# Underglow.net
KiCad netlist of a schematic drawn in Altium Designer
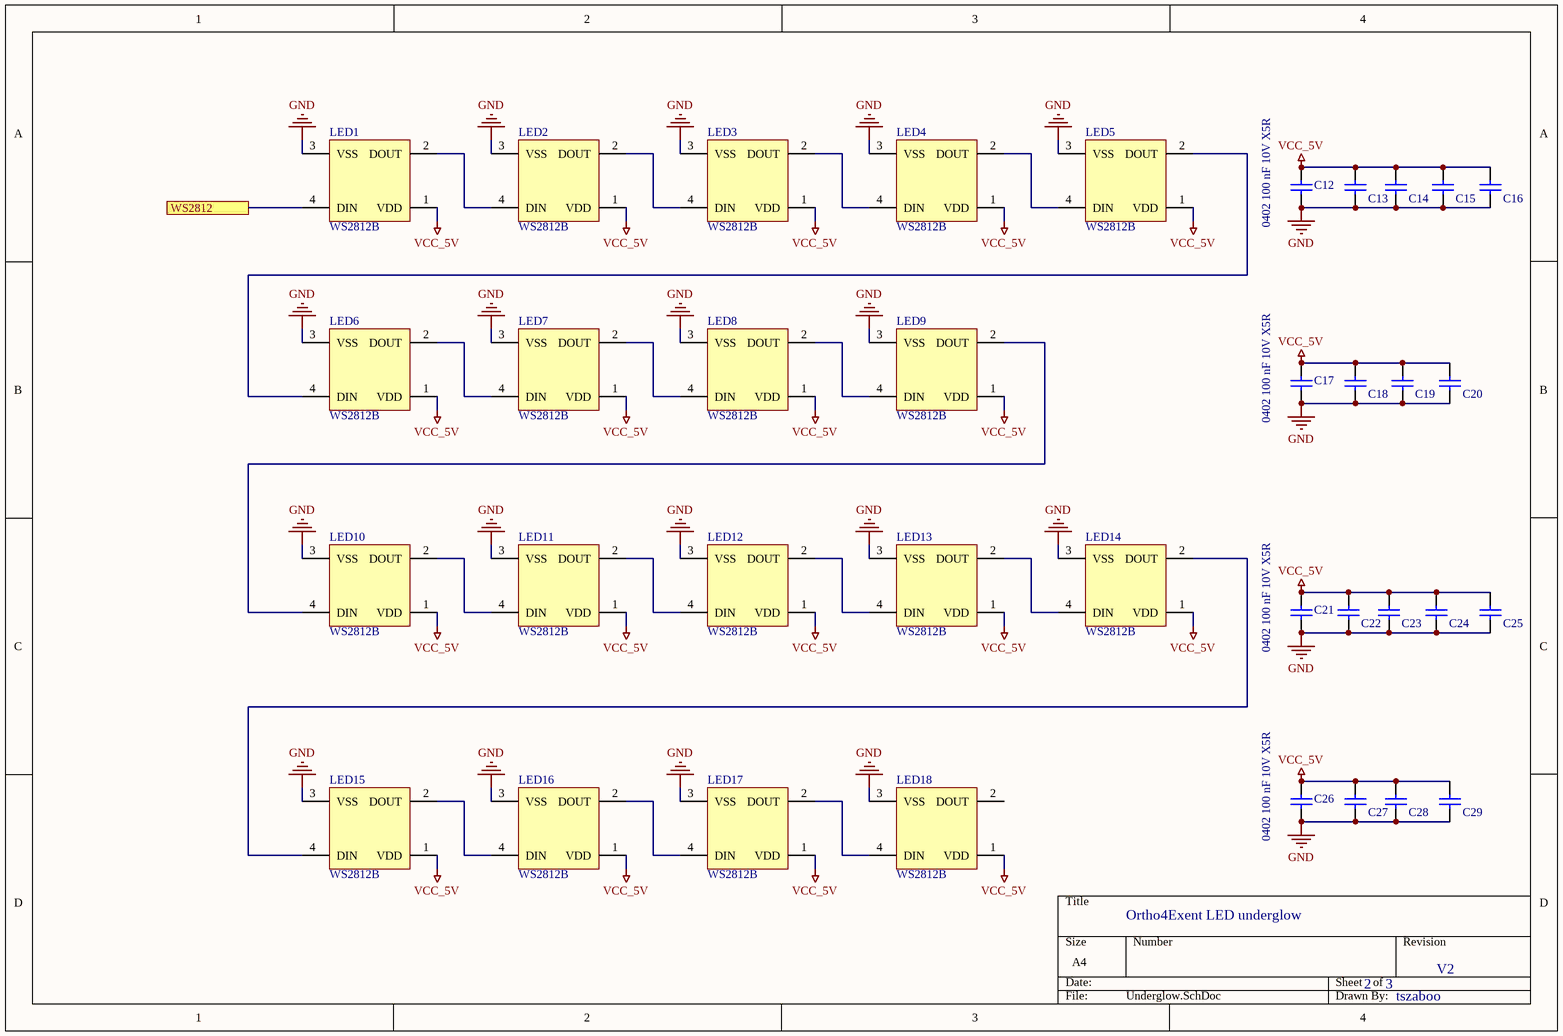
[diagram p0: Underglow.SchDoc]

(export (version "E")
  (design (tool "Eeschema 10.0.6"))
  (components
    (comp (ref "C12")
      (value "0402 100nF")
      (footprint "CAPC0402N")
      (fields (field (name "SCH") "0402 100 nF 10V X5R") (field (name "VOLTAGE") "10"))
      (libsource (lib "WCAP") (part "Cap"))
    )
    (comp (ref "C13")
      (value "0402 100nF")
      (footprint "CAPC0402N")
      (fields (field (name "VOLTAGE") "10"))
      (libsource (lib "WCAP") (part "Cap"))
    )
    (comp (ref "C14")
      (value "0402 100nF")
      (footprint "CAPC0402N")
      (fields (field (name "VOLTAGE") "10"))
      (libsource (lib "WCAP") (part "Cap"))
    )
    (comp (ref "C15")
      (value "0402 100nF")
      (footprint "CAPC0402N")
      (fields (field (name "VOLTAGE") "10"))
      (libsource (lib "WCAP") (part "Cap"))
    )
    (comp (ref "C16")
      (value "0402 100nF")
      (footprint "CAPC0402N")
      (fields (field (name "VOLTAGE") "10"))
      (libsource (lib "WCAP") (part "Cap"))
    )
    (comp (ref "C17")
      (value "0402 100nF")
      (footprint "CAPC0402N")
      (fields (field (name "SCH") "0402 100 nF 10V X5R") (field (name "VOLTAGE") "10"))
      (libsource (lib "WCAP") (part "Cap"))
    )
    (comp (ref "C18")
      (value "0402 100nF")
      (footprint "CAPC0402N")
      (fields (field (name "VOLTAGE") "10"))
      (libsource (lib "WCAP") (part "Cap"))
    )
    (comp (ref "C19")
      (value "0402 100nF")
      (footprint "CAPC0402N")
      (fields (field (name "VOLTAGE") "10"))
      (libsource (lib "WCAP") (part "Cap"))
    )
    (comp (ref "C20")
      (value "0402 100nF")
      (footprint "CAPC0402N")
      (fields (field (name "VOLTAGE") "10"))
      (libsource (lib "WCAP") (part "Cap"))
    )
    (comp (ref "C21")
      (value "0402 100nF")
      (footprint "CAPC0402N")
      (fields (field (name "SCH") "0402 100 nF 10V X5R") (field (name "VOLTAGE") "10"))
      (libsource (lib "WCAP") (part "Cap"))
    )
    (comp (ref "C22")
      (value "0402 100nF")
      (footprint "CAPC0402N")
      (fields (field (name "VOLTAGE") "10"))
      (libsource (lib "WCAP") (part "Cap"))
    )
    (comp (ref "C23")
      (value "0402 100nF")
      (footprint "CAPC0402N")
      (fields (field (name "VOLTAGE") "10"))
      (libsource (lib "WCAP") (part "Cap"))
    )
    (comp (ref "C24")
      (value "0402 100nF")
      (footprint "CAPC0402N")
      (fields (field (name "VOLTAGE") "10"))
      (libsource (lib "WCAP") (part "Cap"))
    )
    (comp (ref "C25")
      (value "0402 100nF")
      (footprint "CAPC0402N")
      (fields (field (name "VOLTAGE") "10"))
      (libsource (lib "WCAP") (part "Cap"))
    )
    (comp (ref "C26")
      (value "0402 100nF")
      (footprint "CAPC0402N")
      (fields (field (name "SCH") "0402 100 nF 10V X5R") (field (name "VOLTAGE") "10"))
      (libsource (lib "WCAP") (part "Cap"))
    )
    (comp (ref "C27")
      (value "0402 100nF")
      (footprint "CAPC0402N")
      (fields (field (name "VOLTAGE") "10"))
      (libsource (lib "WCAP") (part "Cap"))
    )
    (comp (ref "C28")
      (value "0402 100nF")
      (footprint "CAPC0402N")
      (fields (field (name "VOLTAGE") "10"))
      (libsource (lib "WCAP") (part "Cap"))
    )
    (comp (ref "C29")
      (value "0402 100nF")
      (footprint "CAPC0402N")
      (fields (field (name "VOLTAGE") "10"))
      (libsource (lib "WCAP") (part "Cap"))
    )
    (comp (ref "LED1") (value "WS2812B") (footprint "WS2812") (libsource (lib "WS2812") (part "WS2812")))
    (comp (ref "LED2") (value "WS2812B") (footprint "WS2812") (libsource (lib "WS2812") (part "WS2812")))
    (comp (ref "LED3") (value "WS2812B") (footprint "WS2812") (libsource (lib "WS2812") (part "WS2812")))
    (comp (ref "LED4") (value "WS2812B") (footprint "WS2812") (libsource (lib "WS2812") (part "WS2812")))
    (comp (ref "LED5") (value "WS2812B") (footprint "WS2812") (libsource (lib "WS2812") (part "WS2812")))
    (comp (ref "LED6") (value "WS2812B") (footprint "WS2812") (libsource (lib "WS2812") (part "WS2812")))
    (comp (ref "LED7") (value "WS2812B") (footprint "WS2812") (libsource (lib "WS2812") (part "WS2812")))
    (comp (ref "LED8") (value "WS2812B") (footprint "WS2812") (libsource (lib "WS2812") (part "WS2812")))
    (comp (ref "LED9") (value "WS2812B") (footprint "WS2812") (libsource (lib "WS2812") (part "WS2812")))
    (comp (ref "LED10") (value "WS2812B") (footprint "WS2812") (libsource (lib "WS2812") (part "WS2812")))
    (comp (ref "LED11") (value "WS2812B") (footprint "WS2812") (libsource (lib "WS2812") (part "WS2812")))
    (comp (ref "LED12") (value "WS2812B") (footprint "WS2812") (libsource (lib "WS2812") (part "WS2812")))
    (comp (ref "LED13") (value "WS2812B") (footprint "WS2812") (libsource (lib "WS2812") (part "WS2812")))
    (comp (ref "LED14") (value "WS2812B") (footprint "WS2812") (libsource (lib "WS2812") (part "WS2812")))
    (comp (ref "LED15") (value "WS2812B") (footprint "WS2812") (libsource (lib "WS2812") (part "WS2812")))
    (comp (ref "LED16") (value "WS2812B") (footprint "WS2812") (libsource (lib "WS2812") (part "WS2812")))
    (comp (ref "LED17") (value "WS2812B") (footprint "WS2812") (libsource (lib "WS2812") (part "WS2812")))
    (comp (ref "LED18") (value "WS2812B") (footprint "WS2812") (libsource (lib "WS2812") (part "WS2812")))
  )
  (nets
    (net (code "1") (name "/WS2812") (class "Default")
      (node (ref "LED1") (pin "4") (pinfunction "DIN_4") (pintype "passive"))
    )
    (net (code "2") (name "GND") (class "Default")
      (node (ref "C12") (pin "1") (pinfunction "1_1") (pintype "passive"))
      (node (ref "C13") (pin "1") (pinfunction "1_1") (pintype "passive"))
      (node (ref "C14") (pin "1") (pinfunction "1_1") (pintype "passive"))
      (node (ref "C15") (pin "1") (pinfunction "1_1") (pintype "passive"))
      (node (ref "C16") (pin "1") (pinfunction "1_1") (pintype "passive"))
      (node (ref "C17") (pin "1") (pinfunction "1_1") (pintype "passive"))
      (node (ref "C18") (pin "1") (pinfunction "1_1") (pintype "passive"))
      (node (ref "C19") (pin "1") (pinfunction "1_1") (pintype "passive"))
      (node (ref "C20") (pin "1") (pinfunction "1_1") (pintype "passive"))
      (node (ref "C21") (pin "1") (pinfunction "1_1") (pintype "passive"))
      (node (ref "C22") (pin "1") (pinfunction "1_1") (pintype "passive"))
      (node (ref "C23") (pin "1") (pinfunction "1_1") (pintype "passive"))
      (node (ref "C24") (pin "1") (pinfunction "1_1") (pintype "passive"))
      (node (ref "C25") (pin "1") (pinfunction "1_1") (pintype "passive"))
      (node (ref "C26") (pin "1") (pinfunction "1_1") (pintype "passive"))
      (node (ref "C27") (pin "1") (pinfunction "1_1") (pintype "passive"))
      (node (ref "C28") (pin "1") (pinfunction "1_1") (pintype "passive"))
      (node (ref "C29") (pin "1") (pinfunction "1_1") (pintype "passive"))
      (node (ref "LED1") (pin "3") (pinfunction "VSS_3") (pintype "passive"))
      (node (ref "LED10") (pin "3") (pinfunction "VSS_3") (pintype "passive"))
      (node (ref "LED11") (pin "3") (pinfunction "VSS_3") (pintype "passive"))
      (node (ref "LED12") (pin "3") (pinfunction "VSS_3") (pintype "passive"))
      (node (ref "LED13") (pin "3") (pinfunction "VSS_3") (pintype "passive"))
      (node (ref "LED14") (pin "3") (pinfunction "VSS_3") (pintype "passive"))
      (node (ref "LED15") (pin "3") (pinfunction "VSS_3") (pintype "passive"))
      (node (ref "LED16") (pin "3") (pinfunction "VSS_3") (pintype "passive"))
      (node (ref "LED17") (pin "3") (pinfunction "VSS_3") (pintype "passive"))
      (node (ref "LED18") (pin "3") (pinfunction "VSS_3") (pintype "passive"))
      (node (ref "LED2") (pin "3") (pinfunction "VSS_3") (pintype "passive"))
      (node (ref "LED3") (pin "3") (pinfunction "VSS_3") (pintype "passive"))
      (node (ref "LED4") (pin "3") (pinfunction "VSS_3") (pintype "passive"))
      (node (ref "LED5") (pin "3") (pinfunction "VSS_3") (pintype "passive"))
      (node (ref "LED6") (pin "3") (pinfunction "VSS_3") (pintype "passive"))
      (node (ref "LED7") (pin "3") (pinfunction "VSS_3") (pintype "passive"))
      (node (ref "LED8") (pin "3") (pinfunction "VSS_3") (pintype "passive"))
      (node (ref "LED9") (pin "3") (pinfunction "VSS_3") (pintype "passive"))
    )
    (net (code "3") (name "Net-(LED1-DOUT)") (class "Default")
      (node (ref "LED1") (pin "2") (pinfunction "DOUT_2") (pintype "passive"))
      (node (ref "LED2") (pin "4") (pinfunction "DIN_4") (pintype "passive"))
    )
    (net (code "4") (name "Net-(LED2-DOUT)") (class "Default")
      (node (ref "LED2") (pin "2") (pinfunction "DOUT_2") (pintype "passive"))
      (node (ref "LED3") (pin "4") (pinfunction "DIN_4") (pintype "passive"))
    )
    (net (code "5") (name "Net-(LED3-DOUT)") (class "Default")
      (node (ref "LED3") (pin "2") (pinfunction "DOUT_2") (pintype "passive"))
      (node (ref "LED4") (pin "4") (pinfunction "DIN_4") (pintype "passive"))
    )
    (net (code "6") (name "Net-(LED4-DOUT)") (class "Default")
      (node (ref "LED4") (pin "2") (pinfunction "DOUT_2") (pintype "passive"))
      (node (ref "LED5") (pin "4") (pinfunction "DIN_4") (pintype "passive"))
    )
    (net (code "7") (name "Net-(LED5-DOUT)") (class "Default")
      (node (ref "LED5") (pin "2") (pinfunction "DOUT_2") (pintype "passive"))
      (node (ref "LED6") (pin "4") (pinfunction "DIN_4") (pintype "passive"))
    )
    (net (code "8") (name "Net-(LED6-DOUT)") (class "Default")
      (node (ref "LED6") (pin "2") (pinfunction "DOUT_2") (pintype "passive"))
      (node (ref "LED7") (pin "4") (pinfunction "DIN_4") (pintype "passive"))
    )
    (net (code "9") (name "Net-(LED7-DOUT)") (class "Default")
      (node (ref "LED7") (pin "2") (pinfunction "DOUT_2") (pintype "passive"))
      (node (ref "LED8") (pin "4") (pinfunction "DIN_4") (pintype "passive"))
    )
    (net (code "10") (name "Net-(LED8-DOUT)") (class "Default")
      (node (ref "LED8") (pin "2") (pinfunction "DOUT_2") (pintype "passive"))
      (node (ref "LED9") (pin "4") (pinfunction "DIN_4") (pintype "passive"))
    )
    (net (code "11") (name "Net-(LED10-DIN)") (class "Default")
      (node (ref "LED10") (pin "4") (pinfunction "DIN_4") (pintype "passive"))
      (node (ref "LED9") (pin "2") (pinfunction "DOUT_2") (pintype "passive"))
    )
    (net (code "12") (name "Net-(LED10-DOUT)") (class "Default")
      (node (ref "LED10") (pin "2") (pinfunction "DOUT_2") (pintype "passive"))
      (node (ref "LED11") (pin "4") (pinfunction "DIN_4") (pintype "passive"))
    )
    (net (code "13") (name "Net-(LED11-DOUT)") (class "Default")
      (node (ref "LED11") (pin "2") (pinfunction "DOUT_2") (pintype "passive"))
      (node (ref "LED12") (pin "4") (pinfunction "DIN_4") (pintype "passive"))
    )
    (net (code "14") (name "Net-(LED12-DOUT)") (class "Default")
      (node (ref "LED12") (pin "2") (pinfunction "DOUT_2") (pintype "passive"))
      (node (ref "LED13") (pin "4") (pinfunction "DIN_4") (pintype "passive"))
    )
    (net (code "15") (name "Net-(LED13-DOUT)") (class "Default")
      (node (ref "LED13") (pin "2") (pinfunction "DOUT_2") (pintype "passive"))
      (node (ref "LED14") (pin "4") (pinfunction "DIN_4") (pintype "passive"))
    )
    (net (code "16") (name "Net-(LED14-DOUT)") (class "Default")
      (node (ref "LED14") (pin "2") (pinfunction "DOUT_2") (pintype "passive"))
      (node (ref "LED15") (pin "4") (pinfunction "DIN_4") (pintype "passive"))
    )
    (net (code "17") (name "Net-(LED15-DOUT)") (class "Default")
      (node (ref "LED15") (pin "2") (pinfunction "DOUT_2") (pintype "passive"))
      (node (ref "LED16") (pin "4") (pinfunction "DIN_4") (pintype "passive"))
    )
    (net (code "18") (name "Net-(LED16-DOUT)") (class "Default")
      (node (ref "LED16") (pin "2") (pinfunction "DOUT_2") (pintype "passive"))
      (node (ref "LED17") (pin "4") (pinfunction "DIN_4") (pintype "passive"))
    )
    (net (code "19") (name "Net-(LED17-DOUT)") (class "Default")
      (node (ref "LED17") (pin "2") (pinfunction "DOUT_2") (pintype "passive"))
      (node (ref "LED18") (pin "4") (pinfunction "DIN_4") (pintype "passive"))
    )
    (net (code "20") (name "VCC_5V") (class "Default")
      (node (ref "C12") (pin "2") (pinfunction "2_2") (pintype "passive"))
      (node (ref "C13") (pin "2") (pinfunction "2_2") (pintype "passive"))
      (node (ref "C14") (pin "2") (pinfunction "2_2") (pintype "passive"))
      (node (ref "C15") (pin "2") (pinfunction "2_2") (pintype "passive"))
      (node (ref "C16") (pin "2") (pinfunction "2_2") (pintype "passive"))
      (node (ref "C17") (pin "2") (pinfunction "2_2") (pintype "passive"))
      (node (ref "C18") (pin "2") (pinfunction "2_2") (pintype "passive"))
      (node (ref "C19") (pin "2") (pinfunction "2_2") (pintype "passive"))
      (node (ref "C20") (pin "2") (pinfunction "2_2") (pintype "passive"))
      (node (ref "C21") (pin "2") (pinfunction "2_2") (pintype "passive"))
      (node (ref "C22") (pin "2") (pinfunction "2_2") (pintype "passive"))
      (node (ref "C23") (pin "2") (pinfunction "2_2") (pintype "passive"))
      (node (ref "C24") (pin "2") (pinfunction "2_2") (pintype "passive"))
      (node (ref "C25") (pin "2") (pinfunction "2_2") (pintype "passive"))
      (node (ref "C26") (pin "2") (pinfunction "2_2") (pintype "passive"))
      (node (ref "C27") (pin "2") (pinfunction "2_2") (pintype "passive"))
      (node (ref "C28") (pin "2") (pinfunction "2_2") (pintype "passive"))
      (node (ref "C29") (pin "2") (pinfunction "2_2") (pintype "passive"))
      (node (ref "LED1") (pin "1") (pinfunction "VDD_1") (pintype "passive"))
      (node (ref "LED10") (pin "1") (pinfunction "VDD_1") (pintype "passive"))
      (node (ref "LED11") (pin "1") (pinfunction "VDD_1") (pintype "passive"))
      (node (ref "LED12") (pin "1") (pinfunction "VDD_1") (pintype "passive"))
      (node (ref "LED13") (pin "1") (pinfunction "VDD_1") (pintype "passive"))
      (node (ref "LED14") (pin "1") (pinfunction "VDD_1") (pintype "passive"))
      (node (ref "LED15") (pin "1") (pinfunction "VDD_1") (pintype "passive"))
      (node (ref "LED16") (pin "1") (pinfunction "VDD_1") (pintype "passive"))
      (node (ref "LED17") (pin "1") (pinfunction "VDD_1") (pintype "passive"))
      (node (ref "LED18") (pin "1") (pinfunction "VDD_1") (pintype "passive"))
      (node (ref "LED2") (pin "1") (pinfunction "VDD_1") (pintype "passive"))
      (node (ref "LED3") (pin "1") (pinfunction "VDD_1") (pintype "passive"))
      (node (ref "LED4") (pin "1") (pinfunction "VDD_1") (pintype "passive"))
      (node (ref "LED5") (pin "1") (pinfunction "VDD_1") (pintype "passive"))
      (node (ref "LED6") (pin "1") (pinfunction "VDD_1") (pintype "passive"))
      (node (ref "LED7") (pin "1") (pinfunction "VDD_1") (pintype "passive"))
      (node (ref "LED8") (pin "1") (pinfunction "VDD_1") (pintype "passive"))
      (node (ref "LED9") (pin "1") (pinfunction "VDD_1") (pintype "passive"))
    )
    (net (code "21") (name "unconnected-(LED18-DOUT-Pad2)") (class "Default")
      (node (ref "LED18") (pin "2") (pinfunction "DOUT_2") (pintype "passive"))
    )
  )
)
